# 4channelRock.net
KiCad netlist of a schematic drawn in EAGLE
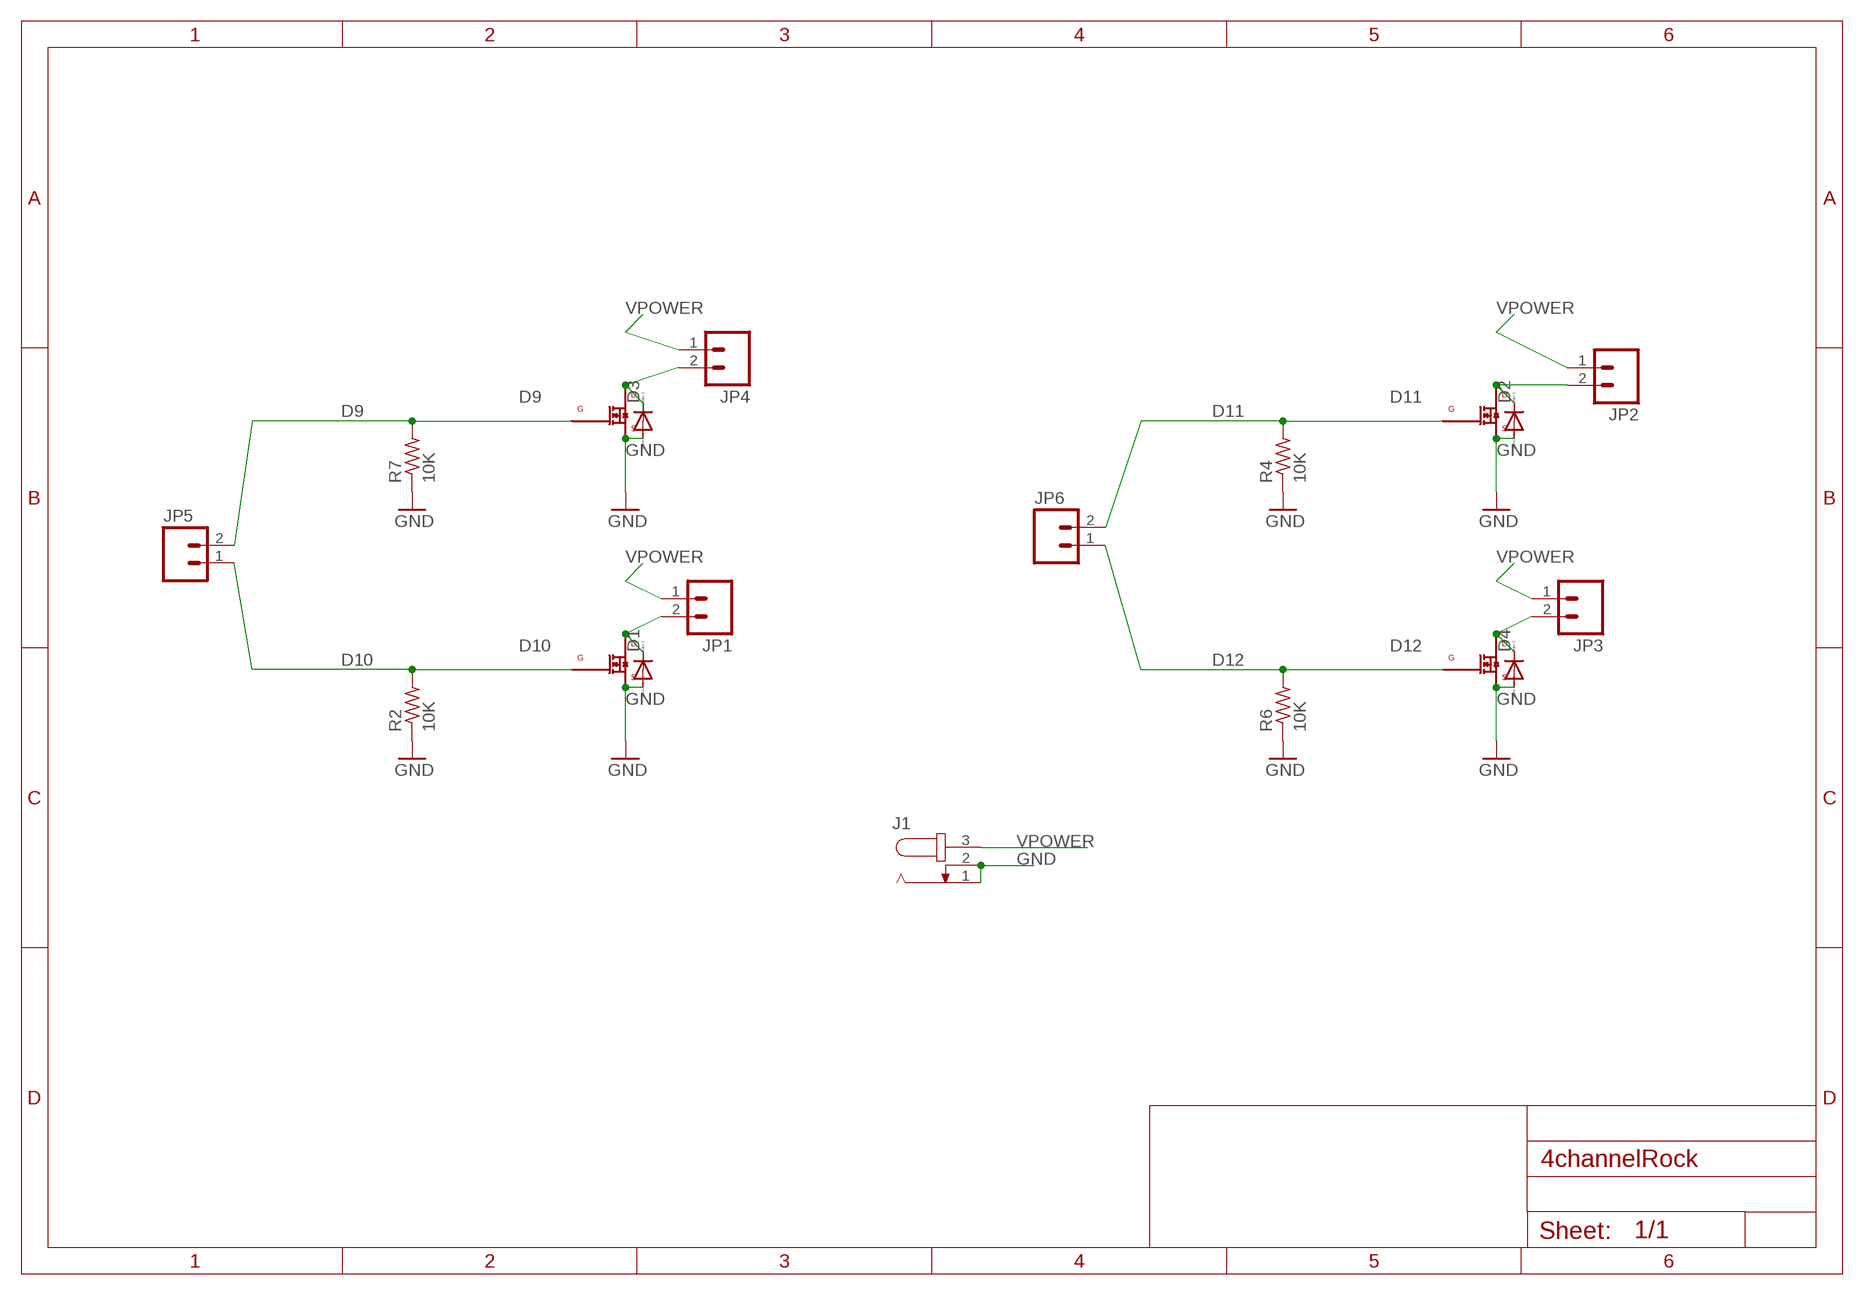
[diagram p0: schematic, sheet 1]

(export (version "E")
  (design (tool "Eeschema 10.0.6"))
  (components
    (comp (ref "D1")
      (value "DIODE-DO-214AC")
      (footprint "eagle-import:DO-214AC")
      (libsource (lib "eagle-import") (part "DIODE-DO-214AC"))
    )
    (comp (ref "D2")
      (value "DIODE-DO-214AC")
      (footprint "eagle-import:DO-214AC")
      (libsource (lib "eagle-import") (part "DIODE-DO-214AC"))
    )
    (comp (ref "D3")
      (value "DIODE-DO-214AC")
      (footprint "eagle-import:DO-214AC")
      (libsource (lib "eagle-import") (part "DIODE-DO-214AC"))
    )
    (comp (ref "D4")
      (value "DIODE-DO-214AC")
      (footprint "eagle-import:DO-214AC")
      (libsource (lib "eagle-import") (part "DIODE-DO-214AC"))
    )
    (comp (ref "J1")
      (value "JACK-PLUG1")
      (footprint "eagle-import:SPC4078")
      (libsource (lib "eagle-import") (part "JACK-PLUG1"))
    )
    (comp (ref "JP1")
      (value "M02PTH")
      (footprint "eagle-import:1X02")
      (libsource (lib "eagle-import") (part "M02PTH"))
    )
    (comp (ref "JP2")
      (value "M02PTH")
      (footprint "eagle-import:1X02")
      (libsource (lib "eagle-import") (part "M02PTH"))
    )
    (comp (ref "JP3")
      (value "M02PTH")
      (footprint "eagle-import:1X02")
      (libsource (lib "eagle-import") (part "M02PTH"))
    )
    (comp (ref "JP4")
      (value "M02PTH")
      (footprint "eagle-import:1X02")
      (libsource (lib "eagle-import") (part "M02PTH"))
    )
    (comp (ref "JP5")
      (value "M02PTH")
      (footprint "eagle-import:1X02")
      (libsource (lib "eagle-import") (part "M02PTH"))
    )
    (comp (ref "JP6")
      (value "M02PTH")
      (footprint "eagle-import:1X02")
      (libsource (lib "eagle-import") (part "M02PTH"))
    )
    (comp (ref "Q1")
      (value "IRLML0060")
      (footprint "eagle-import:SOT-23")
      (libsource (lib "eagle-import") (part "IRLML0060"))
    )
    (comp (ref "Q2")
      (value "IRLML0060")
      (footprint "eagle-import:SOT-23")
      (libsource (lib "eagle-import") (part "IRLML0060"))
    )
    (comp (ref "Q3")
      (value "IRLML0060")
      (footprint "eagle-import:SOT-23")
      (libsource (lib "eagle-import") (part "IRLML0060"))
    )
    (comp (ref "Q4")
      (value "IRLML0060")
      (footprint "eagle-import:SOT-23")
      (libsource (lib "eagle-import") (part "IRLML0060"))
    )
    (comp (ref "R2")
      (value "10K")
      (footprint "eagle-import:R0603")
      (libsource (lib "eagle-import") (part "R-US_R0603"))
    )
    (comp (ref "R4")
      (value "10K")
      (footprint "eagle-import:R0603")
      (libsource (lib "eagle-import") (part "R-US_R0603"))
    )
    (comp (ref "R6")
      (value "10K")
      (footprint "eagle-import:R0603")
      (libsource (lib "eagle-import") (part "R-US_R0603"))
    )
    (comp (ref "R7")
      (value "10K")
      (footprint "eagle-import:R0603")
      (libsource (lib "eagle-import") (part "R-US_R0603"))
    )
  )
  (nets
    (net (code "1") (name "/D9") (class "Default")
      (node (ref "JP5") (pin "2") (pinfunction "2_2") (pintype "passive"))
      (node (ref "Q3") (pin "1") (pinfunction "GATE_1") (pintype "bidirectional"))
      (node (ref "R7") (pin "2") (pinfunction "2_2") (pintype "passive"))
    )
    (net (code "2") (name "/D10") (class "Default")
      (node (ref "JP5") (pin "1") (pinfunction "1_1") (pintype "passive"))
      (node (ref "Q1") (pin "1") (pinfunction "GATE_1") (pintype "bidirectional"))
      (node (ref "R2") (pin "2") (pinfunction "2_2") (pintype "passive"))
    )
    (net (code "3") (name "/D11") (class "Default")
      (node (ref "JP6") (pin "2") (pinfunction "2_2") (pintype "passive"))
      (node (ref "Q2") (pin "1") (pinfunction "GATE_1") (pintype "bidirectional"))
      (node (ref "R4") (pin "2") (pinfunction "2_2") (pintype "passive"))
    )
    (net (code "4") (name "/D12") (class "Default")
      (node (ref "JP6") (pin "1") (pinfunction "1_1") (pintype "passive"))
      (node (ref "Q4") (pin "1") (pinfunction "GATE_1") (pintype "bidirectional"))
      (node (ref "R6") (pin "2") (pinfunction "2_2") (pintype "passive"))
    )
    (net (code "5") (name "/VPOWER") (class "Default")
      (node (ref "J1") (pin "3") (pinfunction "3_3") (pintype "passive"))
      (node (ref "JP1") (pin "1") (pinfunction "1_1") (pintype "passive"))
      (node (ref "JP2") (pin "1") (pinfunction "1_1") (pintype "passive"))
      (node (ref "JP3") (pin "1") (pinfunction "1_1") (pintype "passive"))
      (node (ref "JP4") (pin "1") (pinfunction "1_1") (pintype "passive"))
    )
    (net (code "6") (name "GND") (class "Default")
      (node (ref "D1") (pin "A") (pinfunction "A_A") (pintype "passive"))
      (node (ref "D2") (pin "A") (pinfunction "A_A") (pintype "passive"))
      (node (ref "D3") (pin "A") (pinfunction "A_A") (pintype "passive"))
      (node (ref "D4") (pin "A") (pinfunction "A_A") (pintype "passive"))
      (node (ref "J1") (pin "1") (pinfunction "1_1") (pintype "passive"))
      (node (ref "J1") (pin "2") (pinfunction "2_2") (pintype "passive"))
      (node (ref "Q1") (pin "2") (pinfunction "SOURCE_2") (pintype "bidirectional"))
      (node (ref "Q2") (pin "2") (pinfunction "SOURCE_2") (pintype "bidirectional"))
      (node (ref "Q3") (pin "2") (pinfunction "SOURCE_2") (pintype "bidirectional"))
      (node (ref "Q4") (pin "2") (pinfunction "SOURCE_2") (pintype "bidirectional"))
      (node (ref "R2") (pin "1") (pinfunction "1_1") (pintype "passive"))
      (node (ref "R4") (pin "1") (pinfunction "1_1") (pintype "passive"))
      (node (ref "R6") (pin "1") (pinfunction "1_1") (pintype "passive"))
      (node (ref "R7") (pin "1") (pinfunction "1_1") (pintype "passive"))
    )
    (net (code "7") (name "Net-(Q1-DRAIN)") (class "Default")
      (node (ref "D1") (pin "C") (pinfunction "C_C") (pintype "passive"))
      (node (ref "JP1") (pin "2") (pinfunction "2_2") (pintype "passive"))
      (node (ref "Q1") (pin "3") (pinfunction "DRAIN_3") (pintype "bidirectional"))
    )
    (net (code "8") (name "Net-(Q2-DRAIN)") (class "Default")
      (node (ref "D2") (pin "C") (pinfunction "C_C") (pintype "passive"))
      (node (ref "JP2") (pin "2") (pinfunction "2_2") (pintype "passive"))
      (node (ref "Q2") (pin "3") (pinfunction "DRAIN_3") (pintype "bidirectional"))
    )
    (net (code "9") (name "Net-(Q3-DRAIN)") (class "Default")
      (node (ref "D3") (pin "C") (pinfunction "C_C") (pintype "passive"))
      (node (ref "JP4") (pin "2") (pinfunction "2_2") (pintype "passive"))
      (node (ref "Q3") (pin "3") (pinfunction "DRAIN_3") (pintype "bidirectional"))
    )
    (net (code "10") (name "Net-(Q4-DRAIN)") (class "Default")
      (node (ref "D4") (pin "C") (pinfunction "C_C") (pintype "passive"))
      (node (ref "JP3") (pin "2") (pinfunction "2_2") (pintype "passive"))
      (node (ref "Q4") (pin "3") (pinfunction "DRAIN_3") (pintype "bidirectional"))
    )
  )
)
